# Kobold_--_ATtiny85_and_DRV8830_Combo_--_.net
KiCad netlist of a schematic drawn in EAGLE
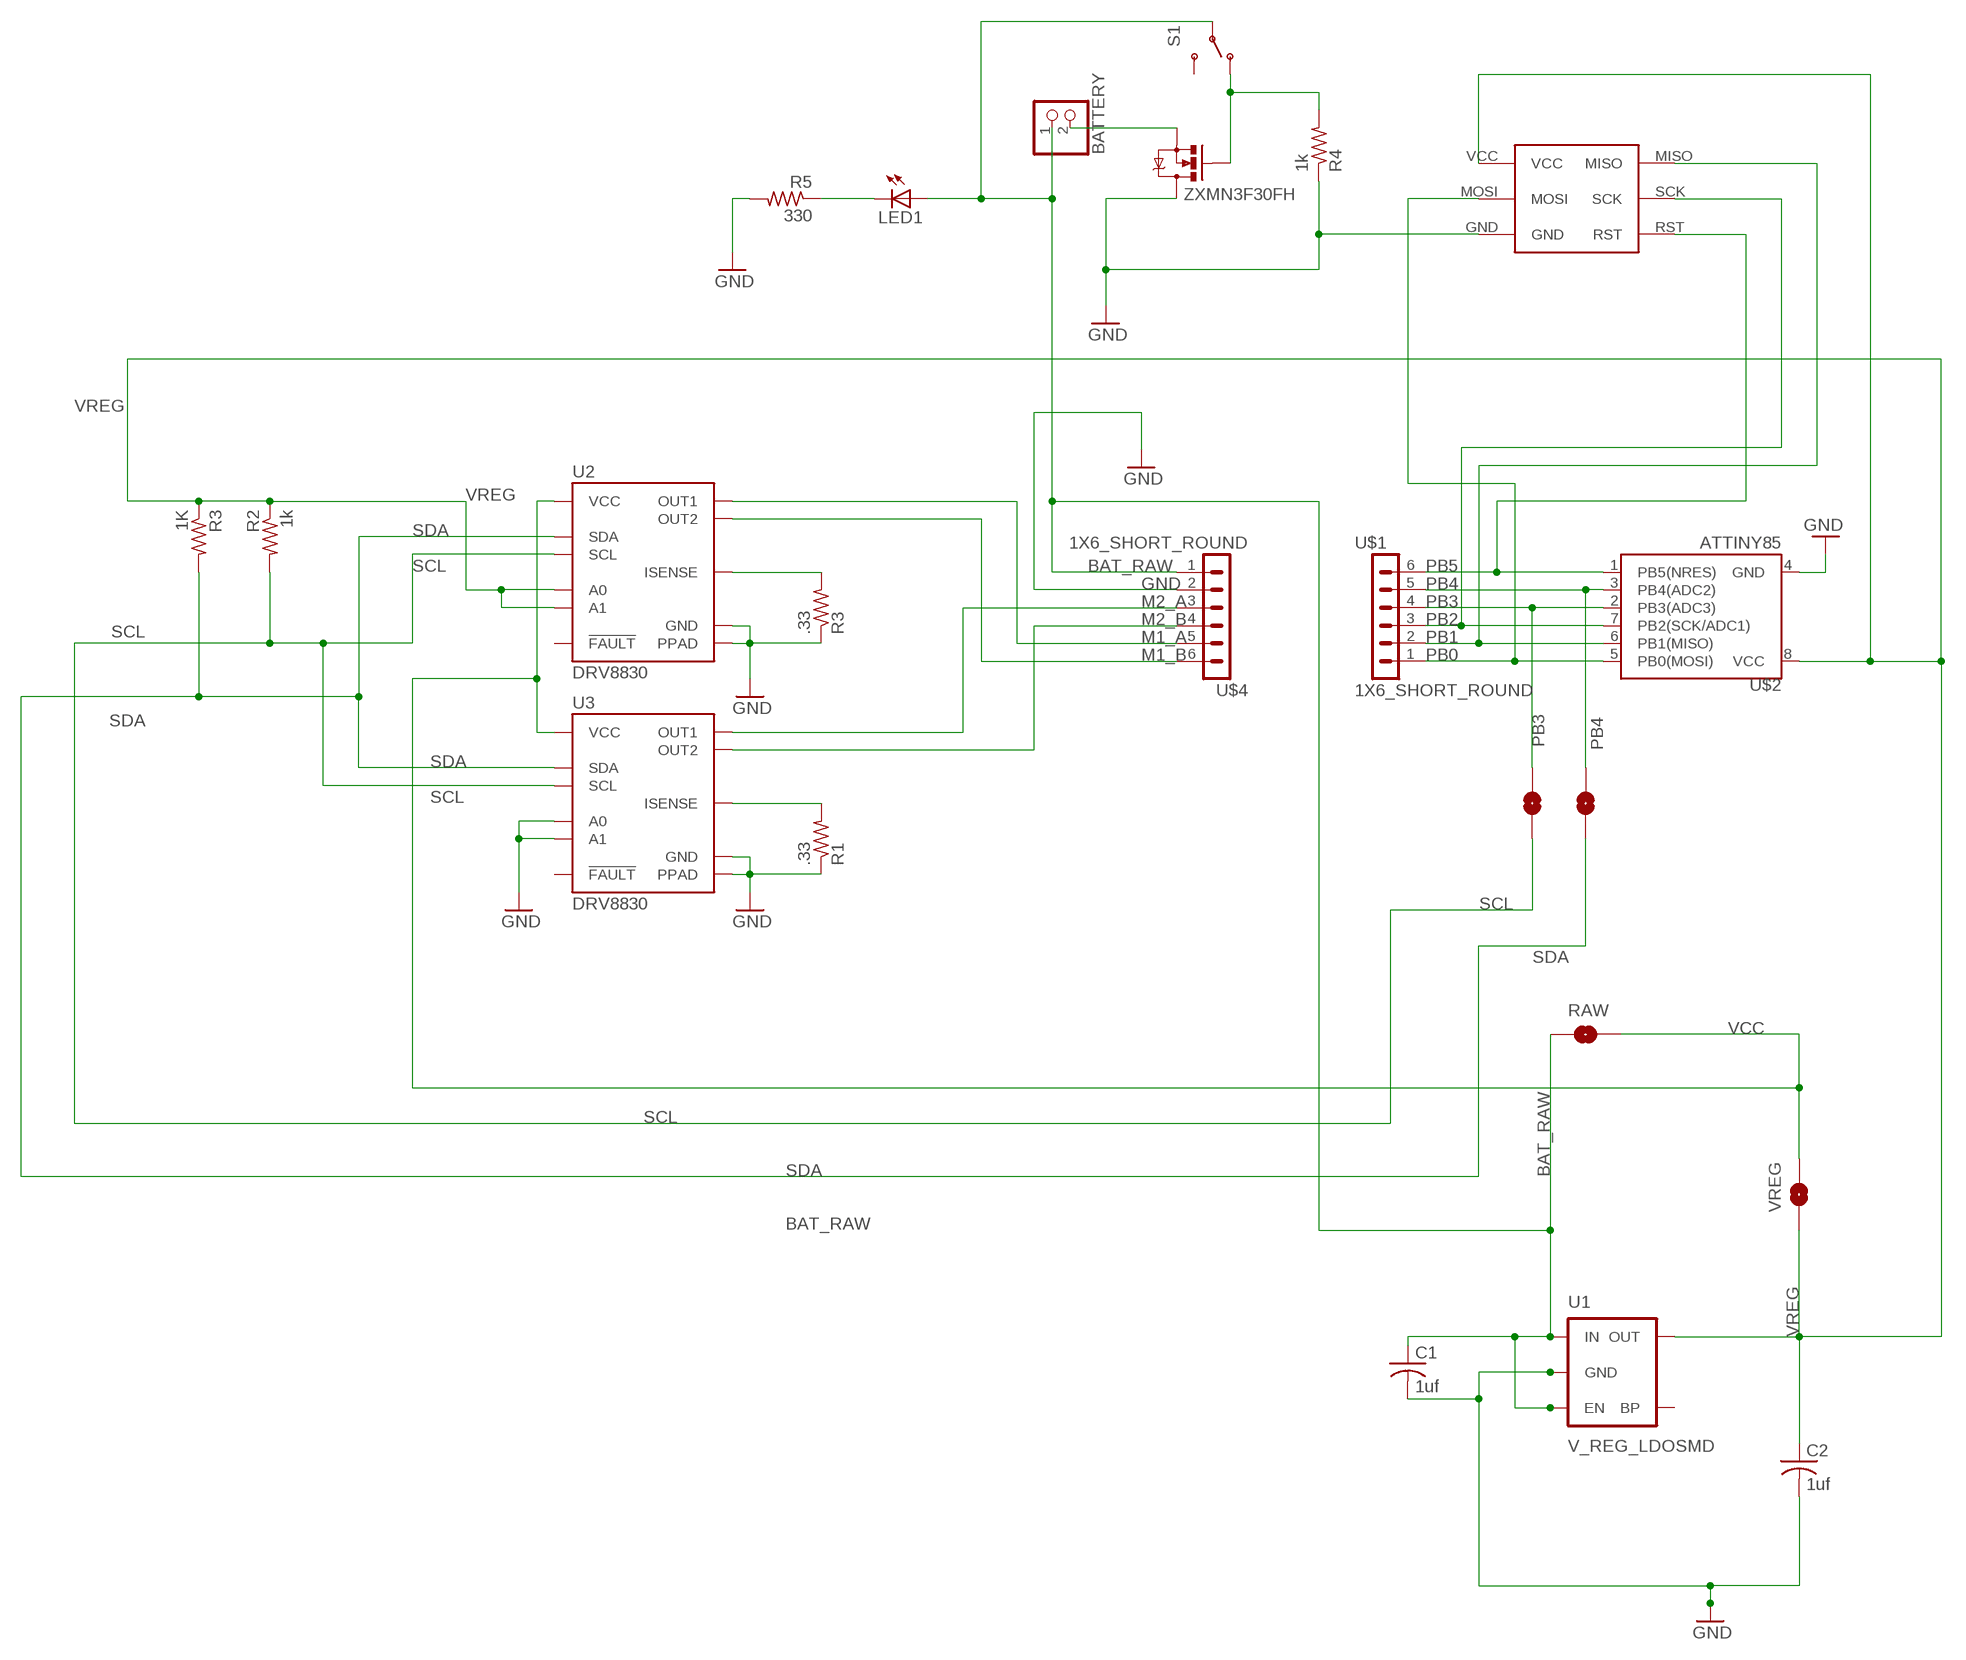
[diagram p0: schematic, sheet 1]

(export (version "E")
  (design (tool "Eeschema 10.0.6"))
  (components
    (comp (ref "1K")
      (value "R3")
      (footprint "eagle-import:R0402")
      (libsource (lib "eagle-import") (part "R-US_R0402"))
    )
    (comp (ref "BATTERY")
      (value "JST_2PIN-THM")
      (footprint "eagle-import:JST-PH-2-THM")
      (libsource (lib "eagle-import") (part "JST_2PIN-THM"))
    )
    (comp (ref "C1")
      (value "1uf")
      (footprint "eagle-import:C0402")
      (libsource (lib "eagle-import") (part "C-USC0402"))
    )
    (comp (ref "C2")
      (value "1uf")
      (footprint "eagle-import:C0402")
      (libsource (lib "eagle-import") (part "C-USC0402"))
    )
    (comp (ref "LED1")
      (value "LEDCHIP-LED0603")
      (footprint "eagle-import:CHIP-LED0603")
      (libsource (lib "eagle-import") (part "LEDCHIP-LED0603"))
    )
    (comp (ref "R1")
      (value ".33")
      (footprint "eagle-import:R0402")
      (libsource (lib "eagle-import") (part "R-US_R0402"))
    )
    (comp (ref "R2")
      (value "1k")
      (footprint "eagle-import:R0402")
      (libsource (lib "eagle-import") (part "R-US_R0402"))
    )
    (comp (ref "R3")
      (value ".33")
      (footprint "eagle-import:R0402")
      (libsource (lib "eagle-import") (part "R-US_R0402"))
    )
    (comp (ref "R4")
      (value "1k")
      (footprint "eagle-import:R0402")
      (libsource (lib "eagle-import") (part "R-US_R0402"))
    )
    (comp (ref "R5")
      (value "330")
      (footprint "eagle-import:R0402")
      (libsource (lib "eagle-import") (part "R-US_R0402"))
    )
    (comp (ref "RAW")
      (value "SOLDERJUMPERNO")
      (footprint "eagle-import:SJ_2S-NO")
      (libsource (lib "eagle-import") (part "SOLDERJUMPERNO"))
    )
    (comp (ref "S1")
      (value "SWITCH-SPDT-SMD-A")
      (footprint "eagle-import:SWITCH-SPST-SMD-A")
      (libsource (lib "eagle-import") (part "SWITCH-SPDT-SMD-A"))
    )
    (comp (ref "SJ6")
      (value "SOLDERJUMPERNO")
      (footprint "eagle-import:SJ_2S-NO")
      (libsource (lib "eagle-import") (part "SOLDERJUMPERNO"))
    )
    (comp (ref "SJ7")
      (value "SOLDERJUMPERNO")
      (footprint "eagle-import:SJ_2S-NO")
      (libsource (lib "eagle-import") (part "SOLDERJUMPERNO"))
    )
    (comp (ref "U$1")
      (value "1X6_SHORT_ROUND")
      (footprint "eagle-import:1X6_SHORT_ROUND")
      (libsource (lib "eagle-import") (part "1X6_SHORT_ROUND"))
    )
    (comp (ref "U$2")
      (value "ATTINY85")
      (footprint "eagle-import:SO08-EIAJ")
      (libsource (lib "eagle-import") (part "ATTINY45"))
    )
    (comp (ref "U$4")
      (value "1X6_SHORT_ROUND")
      (footprint "eagle-import:1X6_SHORT_ROUND")
      (libsource (lib "eagle-import") (part "1X6_SHORT_ROUND"))
    )
    (comp (ref "U$5")
      (value "POGO_PIN_SPI_PAD")
      (footprint "eagle-import:POGO_PIN_SPI_PAD")
      (libsource (lib "eagle-import") (part "POGO_PIN_SPI_PAD"))
    )
    (comp (ref "U1")
      (value "V_REG_LDOSMD")
      (footprint "eagle-import:SOT23-5")
      (libsource (lib "eagle-import") (part "V_REG_LDOSMD"))
    )
    (comp (ref "U2")
      (value "DRV8830")
      (footprint "eagle-import:MSOP-10-GNDPAD")
      (libsource (lib "eagle-import") (part "DRV8830"))
    )
    (comp (ref "U3")
      (value "DRV8830")
      (footprint "eagle-import:MSOP-10-GNDPAD")
      (libsource (lib "eagle-import") (part "DRV8830"))
    )
    (comp (ref "VREG")
      (value "SOLDERJUMPERNO")
      (footprint "eagle-import:SJ_2S-NO")
      (libsource (lib "eagle-import") (part "SOLDERJUMPERNO"))
    )
    (comp (ref "ZXMN3F30FH")
      (value "MOSFET-NCHANNELBSS123LT1G")
      (footprint "eagle-import:SOT23")
      (libsource (lib "eagle-import") (part "MOSFET-NCHANNELBSS123LT1G"))
    )
  )
  (nets
    (net (code "1") (name "/BAT_RAW") (class "Default")
      (node (ref "BATTERY") (pin "1") (pinfunction "2_1") (pintype "passive"))
      (node (ref "C1") (pin "1") (pinfunction "1_1") (pintype "passive"))
      (node (ref "LED1") (pin "A") (pinfunction "A_A") (pintype "passive"))
      (node (ref "RAW") (pin "1") (pinfunction "1_1") (pintype "passive"))
      (node (ref "S1") (pin "2") (pinfunction "P_2") (pintype "passive"))
      (node (ref "U$4") (pin "1") (pinfunction "1_1") (pintype "passive"))
      (node (ref "U1") (pin "1") (pinfunction "IN_1") (pintype "input"))
      (node (ref "U1") (pin "3") (pinfunction "EN_3") (pintype "input"))
    )
    (net (code "2") (name "/M1_A") (class "Default")
      (node (ref "U$4") (pin "5") (pinfunction "5_5") (pintype "passive"))
      (node (ref "U2") (pin "3") (pinfunction "OUT1_3") (pintype "power_in"))
    )
    (net (code "3") (name "/M1_B") (class "Default")
      (node (ref "U$4") (pin "6") (pinfunction "6_6") (pintype "passive"))
      (node (ref "U2") (pin "1") (pinfunction "OUT2_1") (pintype "power_in"))
    )
    (net (code "4") (name "/M2_A") (class "Default")
      (node (ref "U$4") (pin "3") (pinfunction "3_3") (pintype "passive"))
      (node (ref "U3") (pin "3") (pinfunction "OUT1_3") (pintype "power_in"))
    )
    (net (code "5") (name "/M2_B") (class "Default")
      (node (ref "U$4") (pin "4") (pinfunction "4_4") (pintype "passive"))
      (node (ref "U3") (pin "1") (pinfunction "OUT2_1") (pintype "power_in"))
    )
    (net (code "6") (name "/PB0") (class "Default")
      (node (ref "U$1") (pin "1") (pinfunction "1_1") (pintype "passive"))
      (node (ref "U$2") (pin "5") (pinfunction "PB0(MOSI)_5") (pintype "bidirectional"))
      (node (ref "U$5") (pin "MOSI") (pinfunction "MOSI_MOSI") (pintype "bidirectional"))
    )
    (net (code "7") (name "/PB1") (class "Default")
      (node (ref "U$1") (pin "2") (pinfunction "2_2") (pintype "passive"))
      (node (ref "U$2") (pin "6") (pinfunction "PB1(MISO)_6") (pintype "bidirectional"))
      (node (ref "U$5") (pin "MISO") (pinfunction "MISO_MISO") (pintype "bidirectional"))
    )
    (net (code "8") (name "/PB2") (class "Default")
      (node (ref "U$1") (pin "3") (pinfunction "3_3") (pintype "passive"))
      (node (ref "U$2") (pin "7") (pinfunction "PB2(SCK/ADC1)_7") (pintype "bidirectional"))
      (node (ref "U$5") (pin "SCK") (pinfunction "SCK_SCK") (pintype "bidirectional"))
    )
    (net (code "9") (name "/PB3") (class "Default")
      (node (ref "SJ7") (pin "2") (pinfunction "2_2") (pintype "passive"))
      (node (ref "U$1") (pin "4") (pinfunction "4_4") (pintype "passive"))
      (node (ref "U$2") (pin "2") (pinfunction "PB3(ADC3)_2") (pintype "bidirectional"))
    )
    (net (code "10") (name "/PB4") (class "Default")
      (node (ref "SJ6") (pin "2") (pinfunction "2_2") (pintype "passive"))
      (node (ref "U$1") (pin "5") (pinfunction "5_5") (pintype "passive"))
      (node (ref "U$2") (pin "3") (pinfunction "PB4(ADC2)_3") (pintype "bidirectional"))
    )
    (net (code "11") (name "/PB5") (class "Default")
      (node (ref "U$1") (pin "6") (pinfunction "6_6") (pintype "passive"))
      (node (ref "U$2") (pin "1") (pinfunction "PB5(NRES)_1") (pintype "bidirectional"))
      (node (ref "U$5") (pin "RST") (pinfunction "RST_RST") (pintype "bidirectional"))
    )
    (net (code "12") (name "/SCL") (class "Default")
      (node (ref "R2") (pin "2") (pinfunction "2_2") (pintype "passive"))
      (node (ref "SJ7") (pin "1") (pinfunction "1_1") (pintype "passive"))
      (node (ref "U2") (pin "10") (pinfunction "SCL_10") (pintype "input"))
      (node (ref "U3") (pin "10") (pinfunction "SCL_10") (pintype "input"))
    )
    (net (code "13") (name "/SDA") (class "Default")
      (node (ref "1K") (pin "2") (pinfunction "2_2") (pintype "passive"))
      (node (ref "SJ6") (pin "1") (pinfunction "1_1") (pintype "passive"))
      (node (ref "U2") (pin "9") (pinfunction "SDA_9") (pintype "bidirectional"))
      (node (ref "U3") (pin "9") (pinfunction "SDA_9") (pintype "bidirectional"))
    )
    (net (code "14") (name "/VCC") (class "Default")
      (node (ref "RAW") (pin "2") (pinfunction "2_2") (pintype "passive"))
      (node (ref "U2") (pin "4") (pinfunction "VCC_4") (pintype "power_in"))
      (node (ref "U3") (pin "4") (pinfunction "VCC_4") (pintype "power_in"))
      (node (ref "VREG") (pin "2") (pinfunction "2_2") (pintype "passive"))
    )
    (net (code "15") (name "/VREG") (class "Default")
      (node (ref "1K") (pin "1") (pinfunction "1_1") (pintype "passive"))
      (node (ref "C2") (pin "1") (pinfunction "1_1") (pintype "passive"))
      (node (ref "R2") (pin "1") (pinfunction "1_1") (pintype "passive"))
      (node (ref "U$2") (pin "8") (pinfunction "VCC_8") (pintype "bidirectional"))
      (node (ref "U$5") (pin "VCC") (pinfunction "VCC_VCC") (pintype "bidirectional"))
      (node (ref "U1") (pin "5") (pinfunction "OUT_5") (pintype "passive"))
      (node (ref "U2") (pin "7") (pinfunction "A0_7") (pintype "input"))
      (node (ref "U2") (pin "8") (pinfunction "A1_8") (pintype "input"))
      (node (ref "VREG") (pin "1") (pinfunction "1_1") (pintype "passive"))
    )
    (net (code "16") (name "GND") (class "Default")
      (node (ref "C1") (pin "2") (pinfunction "2_2") (pintype "passive"))
      (node (ref "C2") (pin "2") (pinfunction "2_2") (pintype "passive"))
      (node (ref "R1") (pin "1") (pinfunction "1_1") (pintype "passive"))
      (node (ref "R3") (pin "1") (pinfunction "1_1") (pintype "passive"))
      (node (ref "R4") (pin "1") (pinfunction "1_1") (pintype "passive"))
      (node (ref "R5") (pin "2") (pinfunction "2_2") (pintype "passive"))
      (node (ref "U$2") (pin "4") (pinfunction "GND_4") (pintype "bidirectional"))
      (node (ref "U$4") (pin "2") (pinfunction "2_2") (pintype "passive"))
      (node (ref "U$5") (pin "GND") (pinfunction "GND_GND") (pintype "bidirectional"))
      (node (ref "U1") (pin "2") (pinfunction "GND_2") (pintype "input"))
      (node (ref "U2") (pin "5") (pinfunction "GND_5") (pintype "power_in"))
      (node (ref "U2") (pin "GND") (pinfunction "PPAD_GND") (pintype "power_in"))
      (node (ref "U3") (pin "5") (pinfunction "GND_5") (pintype "power_in"))
      (node (ref "U3") (pin "7") (pinfunction "A0_7") (pintype "input"))
      (node (ref "U3") (pin "8") (pinfunction "A1_8") (pintype "input"))
      (node (ref "U3") (pin "GND") (pinfunction "PPAD_GND") (pintype "power_in"))
      (node (ref "ZXMN3F30FH") (pin "3") (pinfunction "D_3") (pintype "passive"))
    )
    (net (code "17") (name "Net-(BATTERY-1)") (class "Default")
      (node (ref "BATTERY") (pin "2") (pinfunction "1_2") (pintype "passive"))
      (node (ref "ZXMN3F30FH") (pin "2") (pinfunction "S_2") (pintype "passive"))
    )
    (net (code "18") (name "Net-(LED1-PadC)") (class "Default")
      (node (ref "LED1") (pin "C") (pinfunction "C_C") (pintype "passive"))
      (node (ref "R5") (pin "1") (pinfunction "1_1") (pintype "passive"))
    )
    (net (code "19") (name "Net-(S1-O)") (class "Default")
      (node (ref "R4") (pin "2") (pinfunction "2_2") (pintype "passive"))
      (node (ref "S1") (pin "1") (pinfunction "O_1") (pintype "passive"))
      (node (ref "ZXMN3F30FH") (pin "1") (pinfunction "G_1") (pintype "passive"))
    )
    (net (code "20") (name "Net-(U2-ISENSE)") (class "Default")
      (node (ref "R3") (pin "2") (pinfunction "2_2") (pintype "passive"))
      (node (ref "U2") (pin "2") (pinfunction "ISENSE_2") (pintype "bidirectional"))
    )
    (net (code "21") (name "Net-(U3-ISENSE)") (class "Default")
      (node (ref "R1") (pin "2") (pinfunction "2_2") (pintype "passive"))
      (node (ref "U3") (pin "2") (pinfunction "ISENSE_2") (pintype "bidirectional"))
    )
    (net (code "22") (name "unconnected-(S1-S-Pad3)") (class "Default")
      (node (ref "S1") (pin "3") (pinfunction "S_3") (pintype "passive"))
    )
    (net (code "23") (name "unconnected-(U1-BP-Pad4)") (class "Default")
      (node (ref "U1") (pin "4") (pinfunction "BP_4") (pintype "input"))
    )
    (net (code "24") (name "unconnected-(U2-~{FAULT}-Pad6)") (class "Default")
      (node (ref "U2") (pin "6") (pinfunction "~{FAULT}_6") (pintype "output"))
    )
    (net (code "25") (name "unconnected-(U3-~{FAULT}-Pad6)") (class "Default")
      (node (ref "U3") (pin "6") (pinfunction "~{FAULT}_6") (pintype "output"))
    )
  )
)
